# POWER-USB2TTL.net
KiCad netlist of a schematic drawn in Altium Designer
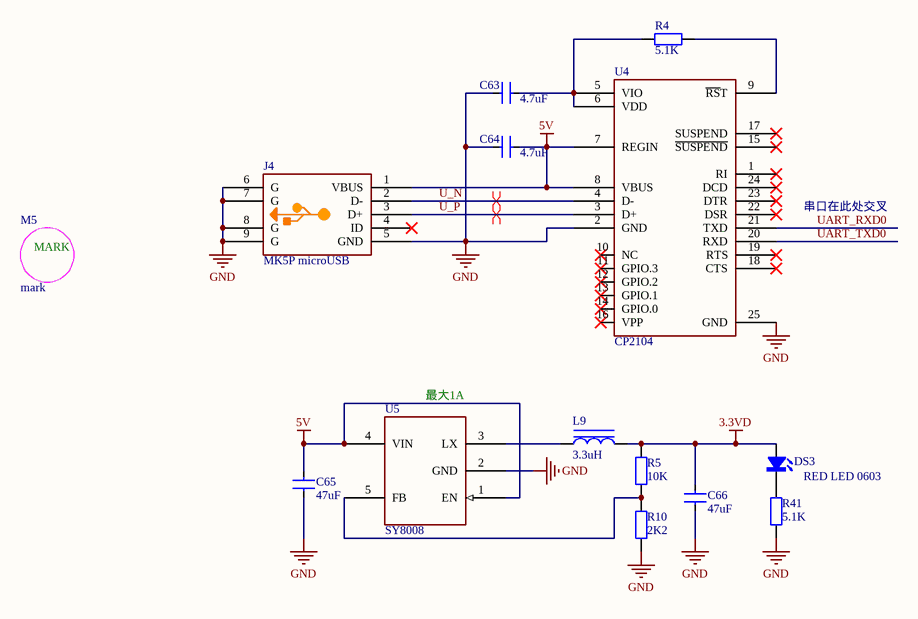
[diagram p0: POWER-USB2TTL.SchDoc]

(export (version "E")
  (design (tool "Eeschema 10.0.6"))
  (components
    (comp (ref "C63")
      (value "4.7uF")
      (footprint "C0402")
      (description "普通小电容")
      (libsource (lib "LIB_MANGO") (part "CAP"))
    )
    (comp (ref "C64")
      (value "4.7uF")
      (footprint "C0402")
      (description "普通小电容")
      (libsource (lib "LIB_MANGO") (part "CAP"))
    )
    (comp (ref "C65")
      (value "47uF")
      (footprint "0805C")
      (description "普通小电容")
      (libsource (lib "LIB_MANGO") (part "CAP"))
    )
    (comp (ref "C66")
      (value "47uF")
      (footprint "0805C")
      (description "普通小电容")
      (libsource (lib "LIB_MANGO") (part "CAP"))
    )
    (comp (ref "DS3")
      (value "RED LED 0603")
      (footprint "LED0603")
      (description "红色0603发光二极管")
      (libsource (lib "LIB_MANGO") (part "LED"))
    )
    (comp (ref "J4")
      (value "MK5P microUSB")
      (footprint "MICROUSB")
      (description "4固定脚microUSB座")
      (libsource (lib "A") (part "MICRO_USB"))
    )
    (comp (ref "L9")
      (value "3.3uH")
      (footprint "VLS3012E")
      (description "vls3012小电感")
      (libsource (lib "LIB_MANGO") (part "L"))
    )
    (comp (ref "M5") (value "mark") (footprint "ZY_UR-3X2") (libsource (lib "LIB_MANGO") (part "mark")))
    (comp (ref "R4")
      (value "5.1K")
      (footprint "R0402")
      (description "普通电阻")
      (libsource (lib "") (part "RES_2"))
    )
    (comp (ref "R5")
      (value "10K")
      (footprint "R0402")
      (description "普通电阻")
      (libsource (lib "LIB_MANGO") (part "RES"))
    )
    (comp (ref "R10")
      (value "2K2")
      (footprint "R0402")
      (description "普通电阻")
      (libsource (lib "LIB_MANGO") (part "RES"))
    )
    (comp (ref "R41")
      (value "5.1K")
      (footprint "R0402")
      (description "普通电阻")
      (libsource (lib "") (part "RES_1"))
    )
    (comp (ref "U4") (value "CP2104") (footprint "QFN24") (libsource (lib "LIB_MANGO") (part "CP2104")))
    (comp (ref "U5") (value "SY8008") (footprint "SOT23-5") (libsource (lib "LIB_MANGO") (part "SY8008")))
  )
  (nets
    (net (code "1") (name "/UART_RXD0") (class "Default")
      (node (ref "U4") (pin "21") (pinfunction "TXD_21") (pintype "passive"))
    )
    (net (code "2") (name "/UART_TXD0") (class "Default")
      (node (ref "U4") (pin "20") (pinfunction "RXD_20") (pintype "passive"))
    )
    (net (code "3") (name "/U_N") (class "Default")
      (node (ref "J4") (pin "2") (pinfunction "D-_2") (pintype "passive"))
      (node (ref "U4") (pin "4") (pinfunction "D-_4") (pintype "passive"))
    )
    (net (code "4") (name "/U_P") (class "Default")
      (node (ref "J4") (pin "3") (pinfunction "D+_3") (pintype "passive"))
      (node (ref "U4") (pin "3") (pinfunction "D+_3") (pintype "passive"))
    )
    (net (code "5") (name "3.3VD") (class "Default")
      (node (ref "C66") (pin "2") (pinfunction "2_2") (pintype "passive"))
      (node (ref "DS3") (pin "A") (pinfunction "1_A") (pintype "passive"))
      (node (ref "L9") (pin "1") (pinfunction "1_1") (pintype "passive"))
      (node (ref "R5") (pin "2") (pinfunction "2_2") (pintype "passive"))
    )
    (net (code "6") (name "5V") (class "Default")
      (node (ref "C64") (pin "2") (pinfunction "2_2") (pintype "passive"))
      (node (ref "C65") (pin "1") (pinfunction "1_1") (pintype "passive"))
      (node (ref "J4") (pin "1") (pinfunction "VBUS_1") (pintype "power_in"))
      (node (ref "U4") (pin "7") (pinfunction "REGIN_7") (pintype "passive"))
      (node (ref "U4") (pin "8") (pinfunction "VBUS_8") (pintype "power_in"))
      (node (ref "U5") (pin "1") (pinfunction "EN_1") (pintype "input"))
      (node (ref "U5") (pin "4") (pinfunction "VIN_4") (pintype "power_in"))
    )
    (net (code "7") (name "GND") (class "Default")
      (node (ref "C63") (pin "2") (pinfunction "2_2") (pintype "passive"))
      (node (ref "C64") (pin "1") (pinfunction "1_1") (pintype "passive"))
      (node (ref "C65") (pin "2") (pinfunction "2_2") (pintype "passive"))
      (node (ref "C66") (pin "1") (pinfunction "1_1") (pintype "passive"))
      (node (ref "J4") (pin "5") (pinfunction "GND_5") (pintype "power_in"))
      (node (ref "J4") (pin "6") (pinfunction "G_6") (pintype "passive"))
      (node (ref "J4") (pin "7") (pinfunction "G_7") (pintype "passive"))
      (node (ref "J4") (pin "8") (pinfunction "G_8") (pintype "passive"))
      (node (ref "J4") (pin "9") (pinfunction "G_9") (pintype "passive"))
      (node (ref "R10") (pin "1") (pinfunction "1_1") (pintype "passive"))
      (node (ref "R41") (pin "2") (pinfunction "2_2") (pintype "passive"))
      (node (ref "U4") (pin "2") (pinfunction "GND_2") (pintype "power_in"))
      (node (ref "U4") (pin "25") (pinfunction "GND_25") (pintype "power_in"))
      (node (ref "U5") (pin "2") (pinfunction "GND_2") (pintype "power_in"))
    )
    (net (code "8") (name "Net-(DS3-2)") (class "Default")
      (node (ref "DS3") (pin "K") (pinfunction "2_K") (pintype "passive"))
      (node (ref "R41") (pin "1") (pinfunction "1_1") (pintype "passive"))
    )
    (net (code "9") (name "Net-(U4-VDD)") (class "Default")
      (node (ref "C63") (pin "1") (pinfunction "1_1") (pintype "passive"))
      (node (ref "R4") (pin "1") (pinfunction "1_1") (pintype "passive"))
      (node (ref "U4") (pin "5") (pinfunction "VIO_5") (pintype "passive"))
      (node (ref "U4") (pin "6") (pinfunction "VDD_6") (pintype "passive"))
    )
    (net (code "10") (name "Net-(U4-~{RS}T)") (class "Default")
      (node (ref "R4") (pin "2") (pinfunction "2_2") (pintype "passive"))
      (node (ref "U4") (pin "9") (pinfunction "~{RS}T_9") (pintype "passive"))
    )
    (net (code "11") (name "Net-(U5-FB)") (class "Default")
      (node (ref "R10") (pin "2") (pinfunction "2_2") (pintype "passive"))
      (node (ref "R5") (pin "1") (pinfunction "1_1") (pintype "passive"))
      (node (ref "U5") (pin "5") (pinfunction "FB_5") (pintype "passive"))
    )
    (net (code "12") (name "Net-(U5-LX)") (class "Default")
      (node (ref "L9") (pin "2") (pinfunction "2_2") (pintype "passive"))
      (node (ref "U5") (pin "3") (pinfunction "LX_3") (pintype "passive"))
    )
    (net (code "13") (name "unconnected-(J4-ID-Pad4)") (class "Default")
      (node (ref "J4") (pin "4") (pinfunction "ID_4") (pintype "passive+no_connect"))
    )
    (net (code "14") (name "unconnected-(U4-CTS-Pad18)") (class "Default")
      (node (ref "U4") (pin "18") (pinfunction "CTS_18") (pintype "passive+no_connect"))
    )
    (net (code "15") (name "unconnected-(U4-DCD-Pad24)") (class "Default")
      (node (ref "U4") (pin "24") (pinfunction "DCD_24") (pintype "passive+no_connect"))
    )
    (net (code "16") (name "unconnected-(U4-DSR-Pad22)") (class "Default")
      (node (ref "U4") (pin "22") (pinfunction "DSR_22") (pintype "passive+no_connect"))
    )
    (net (code "17") (name "unconnected-(U4-DTR-Pad23)") (class "Default")
      (node (ref "U4") (pin "23") (pinfunction "DTR_23") (pintype "passive+no_connect"))
    )
    (net (code "18") (name "unconnected-(U4-GPIO.0-Pad14)") (class "Default")
      (node (ref "U4") (pin "14") (pinfunction "GPIO.0_14") (pintype "passive+no_connect"))
    )
    (net (code "19") (name "unconnected-(U4-GPIO.1-Pad13)") (class "Default")
      (node (ref "U4") (pin "13") (pinfunction "GPIO.1_13") (pintype "passive+no_connect"))
    )
    (net (code "20") (name "unconnected-(U4-GPIO.2-Pad12)") (class "Default")
      (node (ref "U4") (pin "12") (pinfunction "GPIO.2_12") (pintype "passive+no_connect"))
    )
    (net (code "21") (name "unconnected-(U4-GPIO.3-Pad11)") (class "Default")
      (node (ref "U4") (pin "11") (pinfunction "GPIO.3_11") (pintype "passive+no_connect"))
    )
    (net (code "22") (name "unconnected-(U4-NC-Pad10)") (class "Default")
      (node (ref "U4") (pin "10") (pinfunction "NC_10") (pintype "passive+no_connect"))
    )
    (net (code "23") (name "unconnected-(U4-RI-Pad1)") (class "Default")
      (node (ref "U4") (pin "1") (pinfunction "RI_1") (pintype "passive+no_connect"))
    )
    (net (code "24") (name "unconnected-(U4-RTS-Pad19)") (class "Default")
      (node (ref "U4") (pin "19") (pinfunction "RTS_19") (pintype "passive+no_connect"))
    )
    (net (code "25") (name "unconnected-(U4-SUSPEND-Pad17)") (class "Default")
      (node (ref "U4") (pin "17") (pinfunction "SUSPEND_17") (pintype "passive+no_connect"))
    )
    (net (code "26") (name "unconnected-(U4-VPP-Pad16)") (class "Default")
      (node (ref "U4") (pin "16") (pinfunction "VPP_16") (pintype "passive+no_connect"))
    )
    (net (code "27") (name "unconnected-(U4-~{SUSPEND}-Pad15)") (class "Default")
      (node (ref "U4") (pin "15") (pinfunction "~{SUSPEND}_15") (pintype "passive+no_connect"))
    )
  )
)
